# Horn.net
KiCad netlist of a schematic drawn in Altium Designer
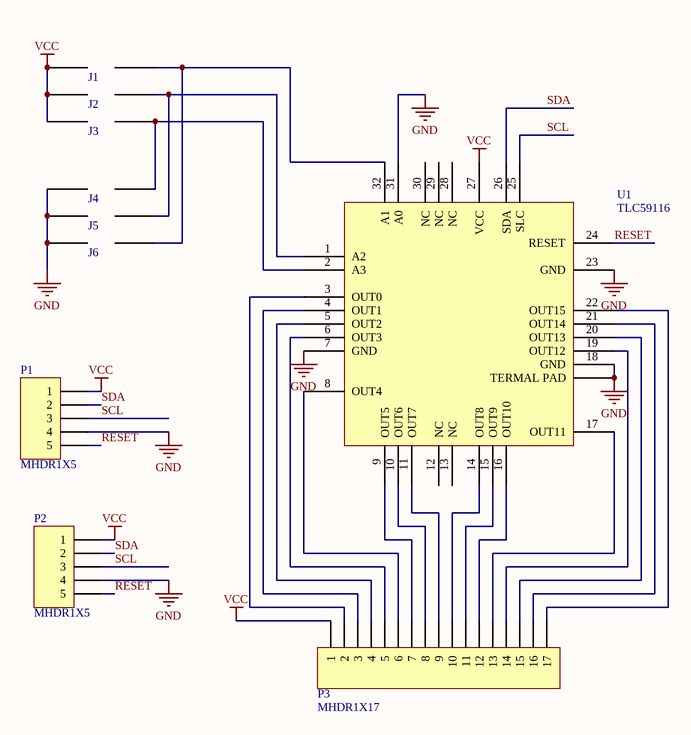
[diagram p0: Horn.SchDoc]

(export (version "E")
  (design (tool "Eeschema 10.0.6"))
  (components
    (comp (ref "J1") (value "Jamper") (footprint "Jumper") (libsource (lib "LockLib") (part "Jamper")))
    (comp (ref "J2") (value "Jamper") (footprint "Jumper") (libsource (lib "LockLib") (part "Jamper")))
    (comp (ref "J3") (value "Jamper") (footprint "Jumper") (libsource (lib "LockLib") (part "Jamper")))
    (comp (ref "J4") (value "Jamper") (footprint "Jumper") (libsource (lib "LockLib") (part "Jamper")))
    (comp (ref "J5") (value "Jamper") (footprint "Jumper") (libsource (lib "LockLib") (part "Jamper")))
    (comp (ref "J6") (value "Jamper") (footprint "Jumper") (libsource (lib "LockLib") (part "Jamper")))
    (comp (ref "P1")
      (value "MHDR1X5")
      (footprint "MHDR1X5")
      (description "Header, 5-Pin")
      (fields (field (name "PUBLISHER") "Altium Limited"))
      (libsource (lib "Miscellaneous Connectors") (part "MHDR1X5"))
    )
    (comp (ref "P2")
      (value "MHDR1X5")
      (footprint "MHDR1X5")
      (description "Header, 5-Pin")
      (fields (field (name "PUBLISHER") "Altium Limited"))
      (libsource (lib "Miscellaneous Connectors") (part "MHDR1X5"))
    )
    (comp (ref "P3")
      (value "MHDR1X17")
      (footprint "MHDR1X17")
      (description "Header, 17-Pin")
      (fields (field (name "PUBLISHER") "Altium Limited"))
      (libsource (lib "Miscellaneous Connectors") (part "MHDR1X17"))
    )
    (comp (ref "U1")
      (value "TLC59116")
      (footprint "QFN50P500X500X100-32N")
      (libsource (lib "LockLib") (part "TLC59116FIRHBR"))
    )
  )
  (nets
    (net (code "1") (name "/RESET") (class "Default")
      (node (ref "P1") (pin "5") (pinfunction "5_5") (pintype "passive"))
      (node (ref "P2") (pin "5") (pinfunction "5_5") (pintype "passive"))
      (node (ref "U1") (pin "24") (pinfunction "RESET_24") (pintype "passive"))
    )
    (net (code "2") (name "/SCL") (class "Default")
      (node (ref "P1") (pin "3") (pinfunction "3_3") (pintype "passive"))
      (node (ref "P2") (pin "3") (pinfunction "3_3") (pintype "passive"))
      (node (ref "U1") (pin "25") (pinfunction "SLC_25") (pintype "passive"))
    )
    (net (code "3") (name "/SDA") (class "Default")
      (node (ref "P1") (pin "2") (pinfunction "2_2") (pintype "passive"))
      (node (ref "P2") (pin "2") (pinfunction "2_2") (pintype "passive"))
      (node (ref "U1") (pin "26") (pinfunction "SDA_26") (pintype "passive"))
    )
    (net (code "4") (name "GND") (class "Default")
      (node (ref "J4") (pin "2") (pintype "passive"))
      (node (ref "J5") (pin "2") (pintype "passive"))
      (node (ref "J6") (pin "2") (pintype "passive"))
      (node (ref "P1") (pin "4") (pinfunction "4_4") (pintype "passive"))
      (node (ref "P2") (pin "4") (pinfunction "4_4") (pintype "passive"))
      (node (ref "U1") (pin "18") (pinfunction "GND_18") (pintype "passive"))
      (node (ref "U1") (pin "23") (pinfunction "GND_23") (pintype "passive"))
      (node (ref "U1") (pin "31") (pinfunction "A0_31") (pintype "passive"))
      (node (ref "U1") (pin "33") (pinfunction "TERMAL_PAD_33") (pintype "passive"))
      (node (ref "U1") (pin "7") (pinfunction "GND_7") (pintype "passive"))
    )
    (net (code "5") (name "Net-(U1-A1)") (class "Default")
      (node (ref "J1") (pin "1") (pintype "passive"))
      (node (ref "J6") (pin "1") (pintype "passive"))
      (node (ref "U1") (pin "32") (pinfunction "A1_32") (pintype "passive"))
    )
    (net (code "6") (name "Net-(U1-A2)") (class "Default")
      (node (ref "J2") (pin "1") (pintype "passive"))
      (node (ref "J5") (pin "1") (pintype "passive"))
      (node (ref "U1") (pin "1") (pinfunction "A2_1") (pintype "passive"))
    )
    (net (code "7") (name "Net-(U1-A3)") (class "Default")
      (node (ref "J3") (pin "1") (pintype "passive"))
      (node (ref "J4") (pin "1") (pintype "passive"))
      (node (ref "U1") (pin "2") (pinfunction "A3_2") (pintype "passive"))
    )
    (net (code "8") (name "Net-(U1-OUT0)") (class "Default")
      (node (ref "P3") (pin "2") (pinfunction "2_2") (pintype "passive"))
      (node (ref "U1") (pin "3") (pinfunction "OUT0_3") (pintype "passive"))
    )
    (net (code "9") (name "Net-(U1-OUT1)") (class "Default")
      (node (ref "P3") (pin "3") (pinfunction "3_3") (pintype "passive"))
      (node (ref "U1") (pin "4") (pinfunction "OUT1_4") (pintype "passive"))
    )
    (net (code "10") (name "Net-(U1-OUT2)") (class "Default")
      (node (ref "P3") (pin "4") (pinfunction "4_4") (pintype "passive"))
      (node (ref "U1") (pin "5") (pinfunction "OUT2_5") (pintype "passive"))
    )
    (net (code "11") (name "Net-(U1-OUT3)") (class "Default")
      (node (ref "P3") (pin "5") (pinfunction "5_5") (pintype "passive"))
      (node (ref "U1") (pin "6") (pinfunction "OUT3_6") (pintype "passive"))
    )
    (net (code "12") (name "Net-(U1-OUT4)") (class "Default")
      (node (ref "P3") (pin "6") (pinfunction "6_6") (pintype "passive"))
      (node (ref "U1") (pin "8") (pinfunction "OUT4_8") (pintype "passive"))
    )
    (net (code "13") (name "Net-(U1-OUT5)") (class "Default")
      (node (ref "P3") (pin "7") (pinfunction "7_7") (pintype "passive"))
      (node (ref "U1") (pin "9") (pinfunction "OUT5_9") (pintype "passive"))
    )
    (net (code "14") (name "Net-(U1-OUT6)") (class "Default")
      (node (ref "P3") (pin "8") (pinfunction "8_8") (pintype "passive"))
      (node (ref "U1") (pin "10") (pinfunction "OUT6_10") (pintype "passive"))
    )
    (net (code "15") (name "Net-(U1-OUT7)") (class "Default")
      (node (ref "P3") (pin "9") (pinfunction "9_9") (pintype "passive"))
      (node (ref "U1") (pin "11") (pinfunction "OUT7_11") (pintype "passive"))
    )
    (net (code "16") (name "Net-(U1-OUT8)") (class "Default")
      (node (ref "P3") (pin "10") (pinfunction "10_10") (pintype "passive"))
      (node (ref "U1") (pin "14") (pinfunction "OUT8_14") (pintype "passive"))
    )
    (net (code "17") (name "Net-(U1-OUT9)") (class "Default")
      (node (ref "P3") (pin "11") (pinfunction "11_11") (pintype "passive"))
      (node (ref "U1") (pin "15") (pinfunction "OUT9_15") (pintype "passive"))
    )
    (net (code "18") (name "Net-(U1-OUT10)") (class "Default")
      (node (ref "P3") (pin "12") (pinfunction "12_12") (pintype "passive"))
      (node (ref "U1") (pin "16") (pinfunction "OUT10_16") (pintype "passive"))
    )
    (net (code "19") (name "Net-(U1-OUT11)") (class "Default")
      (node (ref "P3") (pin "13") (pinfunction "13_13") (pintype "passive"))
      (node (ref "U1") (pin "17") (pinfunction "OUT11_17") (pintype "passive"))
    )
    (net (code "20") (name "Net-(U1-OUT12)") (class "Default")
      (node (ref "P3") (pin "14") (pinfunction "14_14") (pintype "passive"))
      (node (ref "U1") (pin "19") (pinfunction "OUT12_19") (pintype "passive"))
    )
    (net (code "21") (name "Net-(U1-OUT13)") (class "Default")
      (node (ref "P3") (pin "15") (pinfunction "15_15") (pintype "passive"))
      (node (ref "U1") (pin "20") (pinfunction "OUT13_20") (pintype "passive"))
    )
    (net (code "22") (name "Net-(U1-OUT14)") (class "Default")
      (node (ref "P3") (pin "16") (pinfunction "16_16") (pintype "passive"))
      (node (ref "U1") (pin "21") (pinfunction "OUT14_21") (pintype "passive"))
    )
    (net (code "23") (name "Net-(U1-OUT15)") (class "Default")
      (node (ref "P3") (pin "17") (pinfunction "17_17") (pintype "passive"))
      (node (ref "U1") (pin "22") (pinfunction "OUT15_22") (pintype "passive"))
    )
    (net (code "24") (name "VCC") (class "Default")
      (node (ref "J1") (pin "2") (pintype "passive"))
      (node (ref "J2") (pin "2") (pintype "passive"))
      (node (ref "J3") (pin "2") (pintype "passive"))
      (node (ref "P1") (pin "1") (pinfunction "1_1") (pintype "passive"))
      (node (ref "P2") (pin "1") (pinfunction "1_1") (pintype "passive"))
      (node (ref "P3") (pin "1") (pinfunction "1_1") (pintype "passive"))
      (node (ref "U1") (pin "27") (pinfunction "VCC_27") (pintype "passive"))
    )
    (net (code "25") (name "unconnected-(U1-NC-Pad12)") (class "Default")
      (node (ref "U1") (pin "12") (pinfunction "NC_12") (pintype "passive"))
    )
    (net (code "26") (name "unconnected-(U1-NC-Pad13)") (class "Default")
      (node (ref "U1") (pin "13") (pinfunction "NC_13") (pintype "passive"))
    )
    (net (code "27") (name "unconnected-(U1-NC-Pad28)") (class "Default")
      (node (ref "U1") (pin "28") (pinfunction "NC_28") (pintype "passive"))
    )
    (net (code "28") (name "unconnected-(U1-NC-Pad29)") (class "Default")
      (node (ref "U1") (pin "29") (pinfunction "NC_29") (pintype "passive"))
    )
    (net (code "29") (name "unconnected-(U1-NC-Pad30)") (class "Default")
      (node (ref "U1") (pin "30") (pinfunction "NC_30") (pintype "passive"))
    )
  )
)
